# Plotter.net
KiCad netlist of a schematic drawn in EAGLE
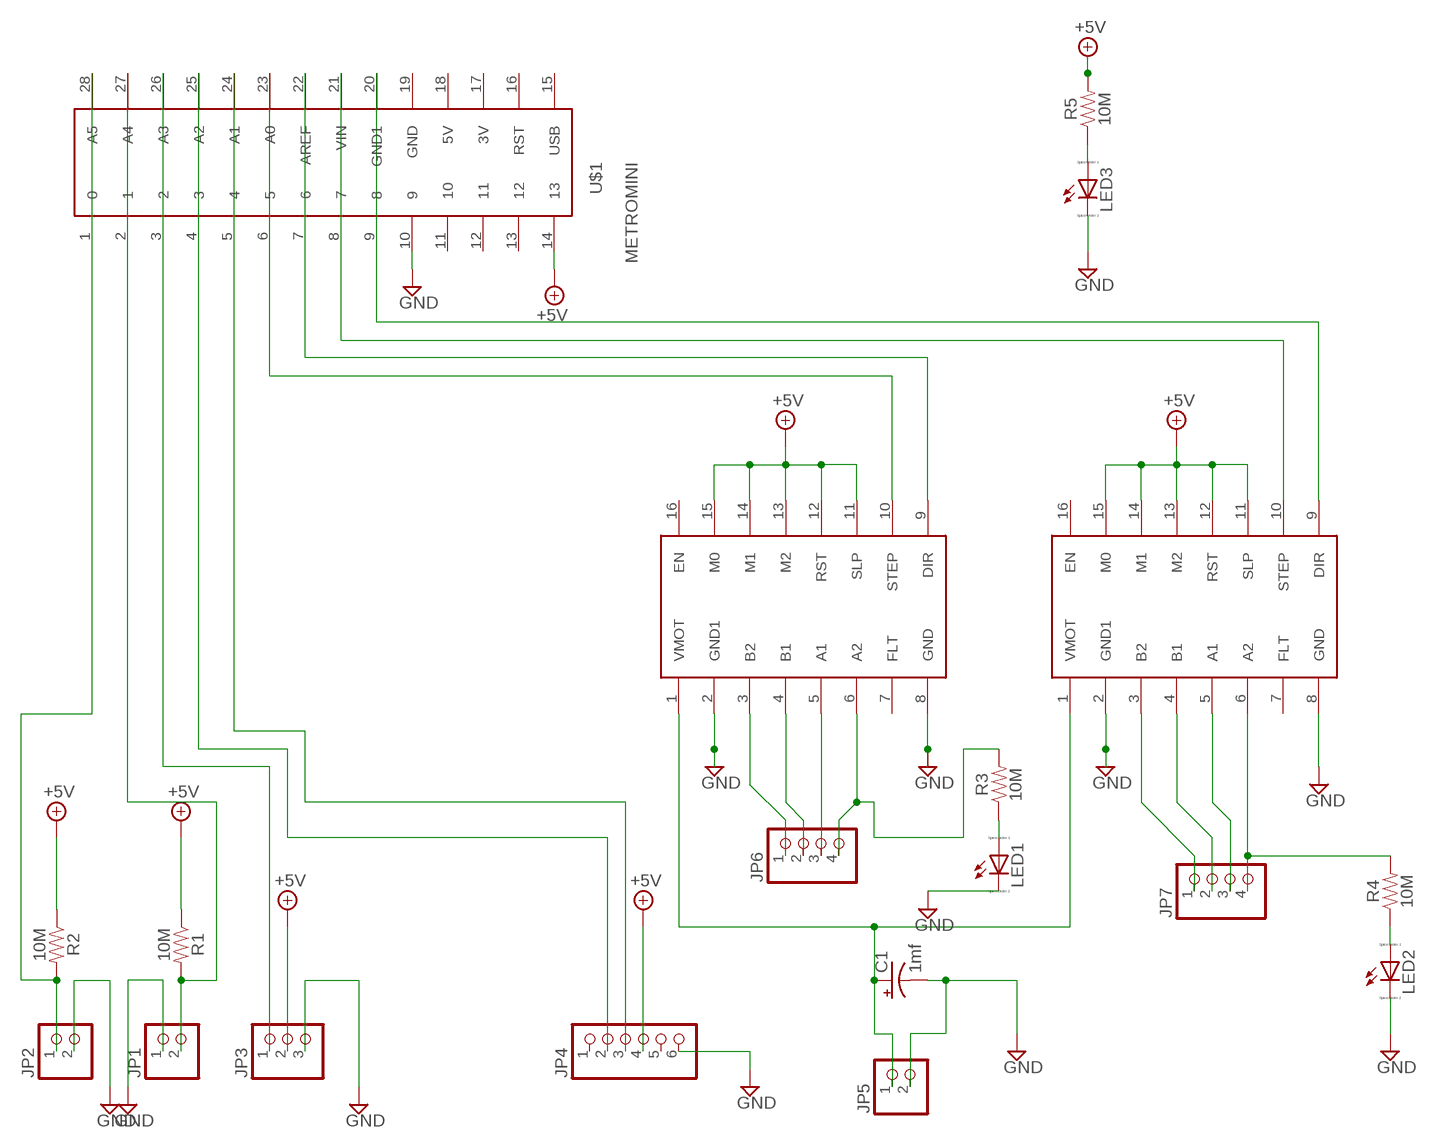
[diagram p0: schematic, sheet 1]

(export (version "E")
  (design (tool "Eeschema 10.0.6"))
  (components
    (comp (ref "C1")
      (value "1mf")
      (footprint "eagle-import:CPOL-RADIAL-5MM-10MM-KIT")
      (libsource (lib "eagle-import") (part "1000UF-RADIAL-5MM-35V-20%-KIT"))
    )
    (comp (ref "JP1")
      (value "PINHD-1X2")
      (footprint "eagle-import:1X02")
      (libsource (lib "eagle-import") (part "PINHD-1X2"))
    )
    (comp (ref "JP2")
      (value "PINHD-1X2")
      (footprint "eagle-import:1X02")
      (libsource (lib "eagle-import") (part "PINHD-1X2"))
    )
    (comp (ref "JP3")
      (value "PINHD-1X3")
      (footprint "eagle-import:1X03")
      (libsource (lib "eagle-import") (part "PINHD-1X3"))
    )
    (comp (ref "JP4")
      (value "PINHD-1X6")
      (footprint "eagle-import:1X06")
      (libsource (lib "eagle-import") (part "PINHD-1X6"))
    )
    (comp (ref "JP5")
      (value "PINHD-1X2")
      (footprint "eagle-import:1X02")
      (libsource (lib "eagle-import") (part "PINHD-1X2"))
    )
    (comp (ref "JP6")
      (value "PINHD-1X4")
      (footprint "eagle-import:1X04")
      (libsource (lib "eagle-import") (part "PINHD-1X4"))
    )
    (comp (ref "JP7")
      (value "PINHD-1X4")
      (footprint "eagle-import:1X04")
      (libsource (lib "eagle-import") (part "PINHD-1X4"))
    )
    (comp (ref "LED1")
      (value "LED_ELD260")
      (footprint "eagle-import:LED_LD260")
      (libsource (lib "eagle-import") (part "LED_ELD260"))
    )
    (comp (ref "LED2")
      (value "LED_ELD260")
      (footprint "eagle-import:LED_LD260")
      (libsource (lib "eagle-import") (part "LED_ELD260"))
    )
    (comp (ref "LED3")
      (value "LED_ELD260")
      (footprint "eagle-import:LED_LD260")
      (libsource (lib "eagle-import") (part "LED_ELD260"))
    )
    (comp (ref "R1")
      (value "10M")
      (footprint "eagle-import:AXIAL-0.3")
      (libsource (lib "eagle-import") (part "10MOHM-HORIZ-1/4W-5%"))
    )
    (comp (ref "R2")
      (value "10M")
      (footprint "eagle-import:AXIAL-0.3")
      (libsource (lib "eagle-import") (part "10MOHM-HORIZ-1/4W-5%"))
    )
    (comp (ref "R3")
      (value "10M")
      (footprint "eagle-import:AXIAL-0.3")
      (libsource (lib "eagle-import") (part "10MOHM-HORIZ-1/4W-5%"))
    )
    (comp (ref "R4")
      (value "10M")
      (footprint "eagle-import:AXIAL-0.3")
      (libsource (lib "eagle-import") (part "10MOHM-HORIZ-1/4W-5%"))
    )
    (comp (ref "R5")
      (value "10M")
      (footprint "eagle-import:AXIAL-0.3")
      (libsource (lib "eagle-import") (part "10MOHM-HORIZ-1/4W-5%"))
    )
    (comp (ref "U$1")
      (value "METROMINI")
      (footprint "eagle-import:METROMINI")
      (libsource (lib "eagle-import") (part "METROMINI"))
    )
    (comp (ref "U$2")
      (value "DRV8825")
      (footprint "eagle-import:DRV8825")
      (libsource (lib "eagle-import") (part "DRV8825"))
    )
    (comp (ref "U$3")
      (value "DRV8825")
      (footprint "eagle-import:DRV8825")
      (libsource (lib "eagle-import") (part "DRV8825"))
    )
  )
  (nets
    (net (code "1") (name "+5V") (class "Default")
      (node (ref "JP3") (pin "2") (pinfunction "2_2") (pintype "passive"))
      (node (ref "JP4") (pin "4") (pinfunction "4_4") (pintype "passive"))
      (node (ref "R1") (pin "P$1") (pinfunction "1_P$1") (pintype "passive"))
      (node (ref "R2") (pin "P$1") (pinfunction "1_P$1") (pintype "passive"))
      (node (ref "R5") (pin "P$2") (pinfunction "2_P$2") (pintype "passive"))
      (node (ref "U$1") (pin "14") (pinfunction "13_14") (pintype "bidirectional"))
      (node (ref "U$2") (pin "11") (pinfunction "SLP_11") (pintype "bidirectional"))
      (node (ref "U$2") (pin "12") (pinfunction "RST_12") (pintype "bidirectional"))
      (node (ref "U$2") (pin "13") (pinfunction "M2_13") (pintype "bidirectional"))
      (node (ref "U$2") (pin "14") (pinfunction "M1_14") (pintype "bidirectional"))
      (node (ref "U$2") (pin "15") (pinfunction "M0_15") (pintype "bidirectional"))
      (node (ref "U$3") (pin "11") (pinfunction "SLP_11") (pintype "bidirectional"))
      (node (ref "U$3") (pin "12") (pinfunction "RST_12") (pintype "bidirectional"))
      (node (ref "U$3") (pin "13") (pinfunction "M2_13") (pintype "bidirectional"))
      (node (ref "U$3") (pin "14") (pinfunction "M1_14") (pintype "bidirectional"))
      (node (ref "U$3") (pin "15") (pinfunction "M0_15") (pintype "bidirectional"))
    )
    (net (code "2") (name "GND") (class "Default")
      (node (ref "C1") (pin "-") (pinfunction "-_-") (pintype "passive"))
      (node (ref "JP1") (pin "1") (pinfunction "1_1") (pintype "passive"))
      (node (ref "JP2") (pin "2") (pinfunction "2_2") (pintype "passive"))
      (node (ref "JP3") (pin "3") (pinfunction "3_3") (pintype "passive"))
      (node (ref "JP4") (pin "6") (pinfunction "6_6") (pintype "passive"))
      (node (ref "JP5") (pin "2") (pinfunction "2_2") (pintype "passive"))
      (node (ref "LED1") (pin "K") (pinfunction "C_K") (pintype "passive"))
      (node (ref "LED2") (pin "K") (pinfunction "C_K") (pintype "passive"))
      (node (ref "LED3") (pin "K") (pinfunction "C_K") (pintype "passive"))
      (node (ref "U$1") (pin "10") (pinfunction "9_10") (pintype "bidirectional"))
      (node (ref "U$2") (pin "2") (pinfunction "GND1_2") (pintype "bidirectional"))
      (node (ref "U$2") (pin "8") (pinfunction "GND_8") (pintype "bidirectional"))
      (node (ref "U$3") (pin "2") (pinfunction "GND1_2") (pintype "bidirectional"))
      (node (ref "U$3") (pin "8") (pinfunction "GND_8") (pintype "bidirectional"))
    )
    (net (code "3") (name "Net-(R1-2)") (class "Default")
      (node (ref "JP1") (pin "2") (pinfunction "2_2") (pintype "passive"))
      (node (ref "R1") (pin "P$2") (pinfunction "2_P$2") (pintype "passive"))
      (node (ref "U$1") (pin "27") (pinfunction "A4_27") (pintype "bidirectional"))
    )
    (net (code "4") (name "Net-(R2-2)") (class "Default")
      (node (ref "JP2") (pin "1") (pinfunction "1_1") (pintype "passive"))
      (node (ref "R2") (pin "P$2") (pinfunction "2_P$2") (pintype "passive"))
      (node (ref "U$1") (pin "28") (pinfunction "A5_28") (pintype "bidirectional"))
    )
    (net (code "5") (name "Net-(R3-1)") (class "Default")
      (node (ref "LED1") (pin "A") (pinfunction "A_A") (pintype "passive"))
      (node (ref "R3") (pin "P$1") (pinfunction "1_P$1") (pintype "passive"))
    )
    (net (code "6") (name "Net-(R3-2)") (class "Default")
      (node (ref "JP6") (pin "4") (pinfunction "4_4") (pintype "passive"))
      (node (ref "R3") (pin "P$2") (pinfunction "2_P$2") (pintype "passive"))
      (node (ref "U$2") (pin "6") (pinfunction "A2_6") (pintype "bidirectional"))
    )
    (net (code "7") (name "Net-(R4-1)") (class "Default")
      (node (ref "LED2") (pin "A") (pinfunction "A_A") (pintype "passive"))
      (node (ref "R4") (pin "P$1") (pinfunction "1_P$1") (pintype "passive"))
    )
    (net (code "8") (name "Net-(R4-2)") (class "Default")
      (node (ref "JP7") (pin "4") (pinfunction "4_4") (pintype "passive"))
      (node (ref "R4") (pin "P$2") (pinfunction "2_P$2") (pintype "passive"))
      (node (ref "U$3") (pin "6") (pinfunction "A2_6") (pintype "bidirectional"))
    )
    (net (code "9") (name "Net-(R5-1)") (class "Default")
      (node (ref "LED3") (pin "A") (pinfunction "A_A") (pintype "passive"))
      (node (ref "R5") (pin "P$1") (pinfunction "1_P$1") (pintype "passive"))
    )
    (net (code "10") (name "Net-(U$1-A0)") (class "Default")
      (node (ref "U$1") (pin "23") (pinfunction "A0_23") (pintype "bidirectional"))
      (node (ref "U$2") (pin "10") (pinfunction "STEP_10") (pintype "bidirectional"))
    )
    (net (code "11") (name "Net-(U$1-A1)") (class "Default")
      (node (ref "JP4") (pin "3") (pinfunction "3_3") (pintype "passive"))
      (node (ref "U$1") (pin "24") (pinfunction "A1_24") (pintype "bidirectional"))
    )
    (net (code "12") (name "Net-(U$1-A2)") (class "Default")
      (node (ref "JP4") (pin "2") (pinfunction "2_2") (pintype "passive"))
      (node (ref "U$1") (pin "25") (pinfunction "A2_25") (pintype "bidirectional"))
    )
    (net (code "13") (name "Net-(U$1-A3)") (class "Default")
      (node (ref "JP3") (pin "1") (pinfunction "1_1") (pintype "passive"))
      (node (ref "U$1") (pin "26") (pinfunction "A3_26") (pintype "bidirectional"))
    )
    (net (code "14") (name "Net-(U$1-AREF)") (class "Default")
      (node (ref "U$1") (pin "22") (pinfunction "AREF_22") (pintype "bidirectional"))
      (node (ref "U$2") (pin "9") (pinfunction "DIR_9") (pintype "bidirectional"))
    )
    (net (code "15") (name "Net-(U$1-GND1)") (class "Default")
      (node (ref "U$1") (pin "20") (pinfunction "GND1_20") (pintype "bidirectional"))
      (node (ref "U$3") (pin "9") (pinfunction "DIR_9") (pintype "bidirectional"))
    )
    (net (code "16") (name "Net-(U$1-VIN)") (class "Default")
      (node (ref "U$1") (pin "21") (pinfunction "VIN_21") (pintype "bidirectional"))
      (node (ref "U$3") (pin "10") (pinfunction "STEP_10") (pintype "bidirectional"))
    )
    (net (code "17") (name "Net-(U$2-A1)") (class "Default")
      (node (ref "JP6") (pin "3") (pinfunction "3_3") (pintype "passive"))
      (node (ref "U$2") (pin "5") (pinfunction "A1_5") (pintype "bidirectional"))
    )
    (net (code "18") (name "Net-(U$2-B1)") (class "Default")
      (node (ref "JP6") (pin "2") (pinfunction "2_2") (pintype "passive"))
      (node (ref "U$2") (pin "4") (pinfunction "B1_4") (pintype "bidirectional"))
    )
    (net (code "19") (name "Net-(U$2-B2)") (class "Default")
      (node (ref "JP6") (pin "1") (pinfunction "1_1") (pintype "passive"))
      (node (ref "U$2") (pin "3") (pinfunction "B2_3") (pintype "bidirectional"))
    )
    (net (code "20") (name "Net-(U$2-VMOT)") (class "Default")
      (node (ref "C1") (pin "+") (pinfunction "+_+") (pintype "passive"))
      (node (ref "JP5") (pin "1") (pinfunction "1_1") (pintype "passive"))
      (node (ref "U$2") (pin "1") (pinfunction "VMOT_1") (pintype "bidirectional"))
      (node (ref "U$3") (pin "1") (pinfunction "VMOT_1") (pintype "bidirectional"))
    )
    (net (code "21") (name "Net-(U$3-A1)") (class "Default")
      (node (ref "JP7") (pin "3") (pinfunction "3_3") (pintype "passive"))
      (node (ref "U$3") (pin "5") (pinfunction "A1_5") (pintype "bidirectional"))
    )
    (net (code "22") (name "Net-(U$3-B1)") (class "Default")
      (node (ref "JP7") (pin "2") (pinfunction "2_2") (pintype "passive"))
      (node (ref "U$3") (pin "4") (pinfunction "B1_4") (pintype "bidirectional"))
    )
    (net (code "23") (name "Net-(U$3-B2)") (class "Default")
      (node (ref "JP7") (pin "1") (pinfunction "1_1") (pintype "passive"))
      (node (ref "U$3") (pin "3") (pinfunction "B2_3") (pintype "bidirectional"))
    )
    (net (code "24") (name "unconnected-(JP4-Pad1)") (class "Default")
      (node (ref "JP4") (pin "1") (pinfunction "1_1") (pintype "passive"))
    )
    (net (code "25") (name "unconnected-(JP4-Pad5)") (class "Default")
      (node (ref "JP4") (pin "5") (pinfunction "5_5") (pintype "passive"))
    )
    (net (code "26") (name "unconnected-(U$1-0-Pad1)") (class "Default")
      (node (ref "U$1") (pin "1") (pinfunction "0_1") (pintype "bidirectional"))
    )
    (net (code "27") (name "unconnected-(U$1-1-Pad2)") (class "Default")
      (node (ref "U$1") (pin "2") (pinfunction "1_2") (pintype "bidirectional"))
    )
    (net (code "28") (name "unconnected-(U$1-2-Pad3)") (class "Default")
      (node (ref "U$1") (pin "3") (pinfunction "2_3") (pintype "bidirectional"))
    )
    (net (code "29") (name "unconnected-(U$1-3-Pad4)") (class "Default")
      (node (ref "U$1") (pin "4") (pinfunction "3_4") (pintype "bidirectional"))
    )
    (net (code "30") (name "unconnected-(U$1-3V-Pad17)") (class "Default")
      (node (ref "U$1") (pin "17") (pinfunction "3V_17") (pintype "bidirectional"))
    )
    (net (code "31") (name "unconnected-(U$1-4-Pad5)") (class "Default")
      (node (ref "U$1") (pin "5") (pinfunction "4_5") (pintype "bidirectional"))
    )
    (net (code "32") (name "unconnected-(U$1-5-Pad6)") (class "Default")
      (node (ref "U$1") (pin "6") (pinfunction "5_6") (pintype "bidirectional"))
    )
    (net (code "33") (name "unconnected-(U$1-5V-Pad18)") (class "Default")
      (node (ref "U$1") (pin "18") (pinfunction "5V_18") (pintype "bidirectional"))
    )
    (net (code "34") (name "unconnected-(U$1-6-Pad7)") (class "Default")
      (node (ref "U$1") (pin "7") (pinfunction "6_7") (pintype "bidirectional"))
    )
    (net (code "35") (name "unconnected-(U$1-7-Pad8)") (class "Default")
      (node (ref "U$1") (pin "8") (pinfunction "7_8") (pintype "bidirectional"))
    )
    (net (code "36") (name "unconnected-(U$1-8-Pad9)") (class "Default")
      (node (ref "U$1") (pin "9") (pinfunction "8_9") (pintype "bidirectional"))
    )
    (net (code "37") (name "unconnected-(U$1-10-Pad11)") (class "Default")
      (node (ref "U$1") (pin "11") (pinfunction "10_11") (pintype "bidirectional"))
    )
    (net (code "38") (name "unconnected-(U$1-11-Pad12)") (class "Default")
      (node (ref "U$1") (pin "12") (pinfunction "11_12") (pintype "bidirectional"))
    )
    (net (code "39") (name "unconnected-(U$1-12-Pad13)") (class "Default")
      (node (ref "U$1") (pin "13") (pinfunction "12_13") (pintype "bidirectional"))
    )
    (net (code "40") (name "unconnected-(U$1-GND-Pad19)") (class "Default")
      (node (ref "U$1") (pin "19") (pinfunction "GND_19") (pintype "bidirectional"))
    )
    (net (code "41") (name "unconnected-(U$1-RST-Pad16)") (class "Default")
      (node (ref "U$1") (pin "16") (pinfunction "RST_16") (pintype "bidirectional"))
    )
    (net (code "42") (name "unconnected-(U$1-USB-Pad15)") (class "Default")
      (node (ref "U$1") (pin "15") (pinfunction "USB_15") (pintype "bidirectional"))
    )
    (net (code "43") (name "unconnected-(U$2-EN-Pad16)") (class "Default")
      (node (ref "U$2") (pin "16") (pinfunction "EN_16") (pintype "bidirectional"))
    )
    (net (code "44") (name "unconnected-(U$2-FLT-Pad7)") (class "Default")
      (node (ref "U$2") (pin "7") (pinfunction "FLT_7") (pintype "bidirectional"))
    )
    (net (code "45") (name "unconnected-(U$3-EN-Pad16)") (class "Default")
      (node (ref "U$3") (pin "16") (pinfunction "EN_16") (pintype "bidirectional"))
    )
    (net (code "46") (name "unconnected-(U$3-FLT-Pad7)") (class "Default")
      (node (ref "U$3") (pin "7") (pinfunction "FLT_7") (pintype "bidirectional"))
    )
  )
)
